# encoder.net
KiCad netlist of a schematic drawn in Altium Designer
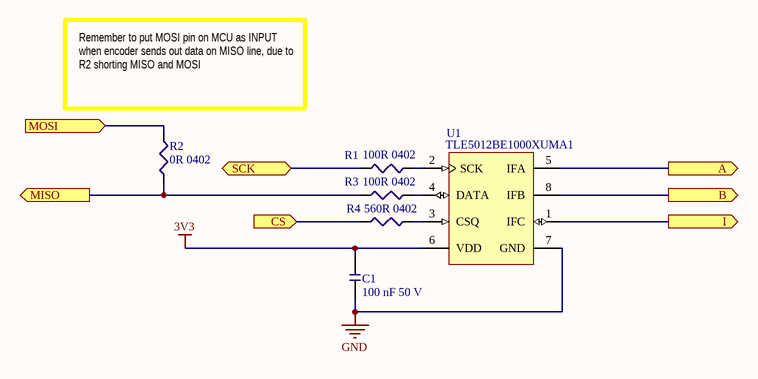
[diagram p0: encoder.SchDoc]

(export (version "E")
  (design (tool "Eeschema 10.0.6"))
  (components
    (comp (ref "C1")
      (value "100 nF 50 V")
      (footprint "CAP_0402")
      (description "Multilayer Ceramic Capacitors MLCC - SMD/SMT .1uF 50Volts X7R +/-10% 0402 STD")
      (fields (field (name "TOLERANCE") "10%") (field (name "VOLTAGE") "50 V"))
      (libsource (lib "ON Development Vault") (part "Capacitor"))
    )
    (comp (ref "R1")
      (value "100R 0402")
      (footprint "RES_0402")
      (description "100R 1% 0402 63mW")
      (fields (field (name "POWER") "63mW") (field (name "TOLERANCE") "1%"))
      (libsource (lib "ON Development Vault") (part "Resistor"))
    )
    (comp (ref "R2")
      (value "0R 0402")
      (footprint "RES_0402")
      (description "RES SMD 0 OHM 1/16W 0402")
      (fields (field (name "POWER") "63mW") (field (name "MFG. PART NUMBER") "RC0402JR-070RL"))
      (libsource (lib "ON Development Vault") (part "Resistor"))
    )
    (comp (ref "R3")
      (value "560R 0402")
      (footprint "RES_0402")
      (description "RES SMD 560 OHM 1% 1/16W 0402")
      (fields (field (name "POWER") "1/16 W") (field (name "TOLERANCE") "1 %"))
      (libsource (lib "ON Development Vault") (part "Resistor"))
    )
    (comp (ref "R4")
      (value "100R 0402")
      (footprint "RES_0402")
      (description "100R 1% 0402 63mW")
      (fields (field (name "POWER") "63mW") (field (name "TOLERANCE") "1%"))
      (libsource (lib "ON Development Vault") (part "Resistor"))
    )
    (comp (ref "U1")
      (value "TLE5012BE1000XUMA1")
      (footprint "INF-PG-DSO-8-16_M")
      (description "Board Mount Hall Effect / Magnetic Sensors GMR Based Angle Sensor 6.5V")
      (libsource (lib "ON Development Vault") (part "INF-TLE5012BEXX-PG-DSO-8"))
    )
  )
  (nets
    (net (code "1") (name "/A") (class "Default")
      (node (ref "U1") (pin "5") (pinfunction "IFA_5") (pintype "open_collector"))
    )
    (net (code "2") (name "/B") (class "Default")
      (node (ref "U1") (pin "8") (pinfunction "IFB_8") (pintype "open_collector"))
    )
    (net (code "3") (name "/CS") (class "Default")
      (node (ref "R4") (pin "1") (pinfunction "1_1") (pintype "passive"))
    )
    (net (code "4") (name "/I") (class "Default")
      (node (ref "U1") (pin "1") (pinfunction "IFC_1") (pintype "bidirectional"))
    )
    (net (code "5") (name "/MISO") (class "Default")
      (node (ref "R2") (pin "1") (pinfunction "1_1") (pintype "passive"))
      (node (ref "R3") (pin "1") (pinfunction "1_1") (pintype "passive"))
    )
    (net (code "6") (name "/MOSI") (class "Default")
      (node (ref "R2") (pin "2") (pinfunction "2_2") (pintype "passive"))
    )
    (net (code "7") (name "/SCK") (class "Default")
      (node (ref "R1") (pin "1") (pinfunction "1_1") (pintype "passive"))
    )
    (net (code "8") (name "3V3") (class "Default")
      (node (ref "C1") (pin "1") (pinfunction "1_1") (pintype "passive"))
      (node (ref "U1") (pin "6") (pinfunction "VDD_6") (pintype "power_in"))
    )
    (net (code "9") (name "GND") (class "Default")
      (node (ref "C1") (pin "2") (pinfunction "2_2") (pintype "passive"))
      (node (ref "U1") (pin "7") (pinfunction "GND_7") (pintype "power_in"))
    )
    (net (code "10") (name "Net-(U1-CSQ)") (class "Default")
      (node (ref "R4") (pin "2") (pinfunction "2_2") (pintype "passive"))
      (node (ref "U1") (pin "3") (pinfunction "CSQ_3") (pintype "input"))
    )
    (net (code "11") (name "Net-(U1-DATA)") (class "Default")
      (node (ref "R3") (pin "2") (pinfunction "2_2") (pintype "passive"))
      (node (ref "U1") (pin "4") (pinfunction "DATA_4") (pintype "bidirectional"))
    )
    (net (code "12") (name "Net-(U1-SCK)") (class "Default")
      (node (ref "R1") (pin "2") (pinfunction "2_2") (pintype "passive"))
      (node (ref "U1") (pin "2") (pinfunction "SCK_2") (pintype "input"))
    )
  )
)
